# ethero_v4.net
KiCad netlist of a schematic drawn in EAGLE
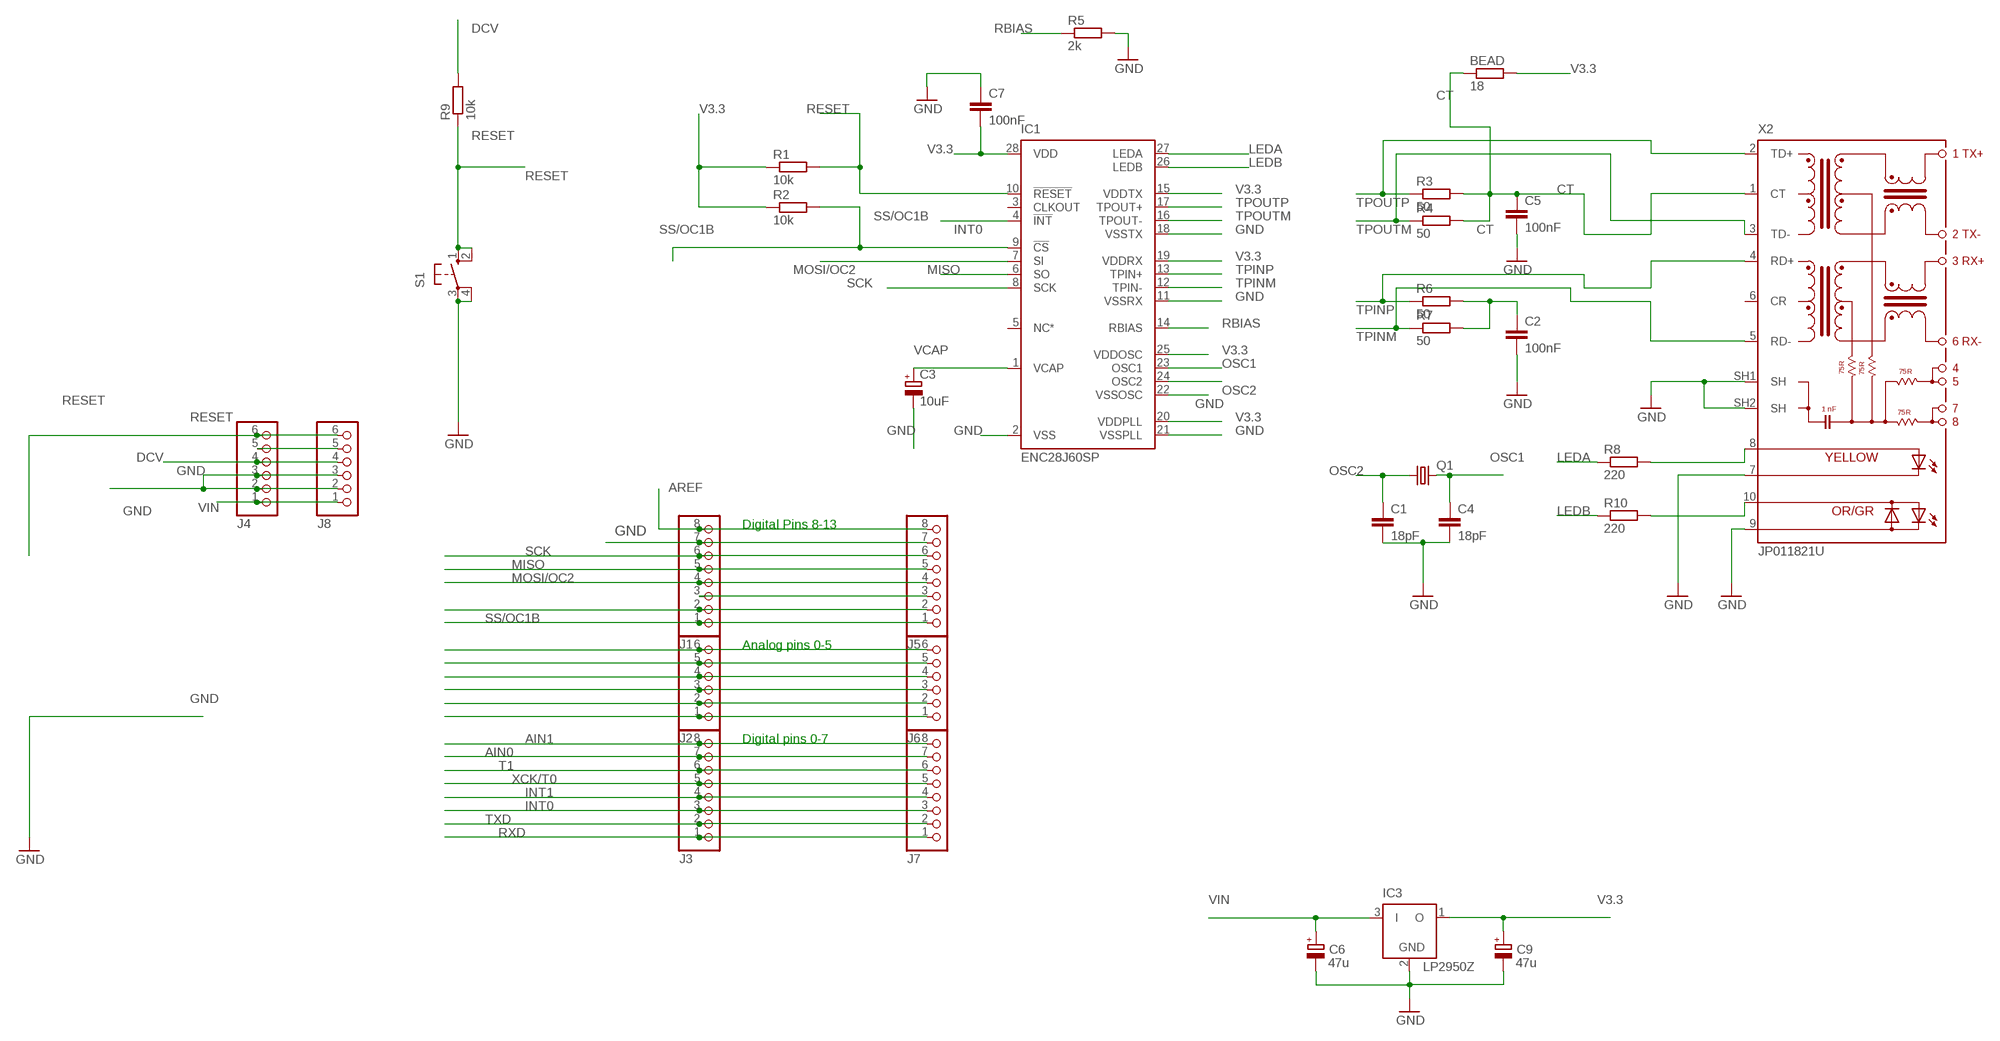
[diagram p0: schematic, sheet 1]

(export (version "E")
  (design (tool "Eeschema 10.0.6"))
  (components
    (comp (ref "BEAD")
      (value "18")
      (footprint "eagle-import:0204_7")
      (libsource (lib "eagle-import") (part "R-EU_0204/7"))
    )
    (comp (ref "C1")
      (value "18pF")
      (footprint "eagle-import:C025-025X050")
      (libsource (lib "eagle-import") (part "C-EU025-025X050"))
    )
    (comp (ref "C2")
      (value "100nF")
      (footprint "eagle-import:C025-025X050")
      (libsource (lib "eagle-import") (part "C-EU025-025X050"))
    )
    (comp (ref "C3")
      (value "10uF")
      (footprint "eagle-import:E5-5")
      (libsource (lib "eagle-import") (part "CPOL-EUE5-5"))
    )
    (comp (ref "C4")
      (value "18pF")
      (footprint "eagle-import:C025-025X050")
      (libsource (lib "eagle-import") (part "C-EU025-025X050"))
    )
    (comp (ref "C5")
      (value "100nF")
      (footprint "eagle-import:C025-025X050")
      (libsource (lib "eagle-import") (part "C-EU025-025X050"))
    )
    (comp (ref "C6")
      (value "47u")
      (footprint "eagle-import:E3,5-8")
      (libsource (lib "eagle-import") (part "CPOL-EUE3.5-8"))
    )
    (comp (ref "C7")
      (value "100nF")
      (footprint "eagle-import:C025-025X050")
      (libsource (lib "eagle-import") (part "C-EU025-025X050"))
    )
    (comp (ref "C9")
      (value "47u")
      (footprint "eagle-import:E3,5-8")
      (libsource (lib "eagle-import") (part "CPOL-EUE3.5-8"))
    )
    (comp (ref "IC1")
      (value "ENC28J60SP")
      (footprint "eagle-import:DIL28-3")
      (fields (field (name "MF") "MICROCHIP") (field (name "MPN") "ENC28J60/SP"))
      (libsource (lib "eagle-import") (part "ENC28J60SP"))
    )
    (comp (ref "IC3")
      (value "LP2950Z")
      (footprint "eagle-import:TO92")
      (libsource (lib "eagle-import") (part "LP2950Z"))
    )
    (comp (ref "J1")
      (value "PINHD-1X8")
      (footprint "eagle-import:1X08")
      (libsource (lib "eagle-import") (part "PINHD-1X8"))
    )
    (comp (ref "J2")
      (value "PINHD-1X6")
      (footprint "eagle-import:1X06")
      (libsource (lib "eagle-import") (part "PINHD-1X6"))
    )
    (comp (ref "J3")
      (value "PINHD-1X8")
      (footprint "eagle-import:1X08")
      (libsource (lib "eagle-import") (part "PINHD-1X8"))
    )
    (comp (ref "J4")
      (value "PINHD-1X6")
      (footprint "eagle-import:1X06")
      (libsource (lib "eagle-import") (part "PINHD-1X6"))
    )
    (comp (ref "J5")
      (value "PINHD-1X8")
      (footprint "eagle-import:1X08")
      (libsource (lib "eagle-import") (part "PINHD-1X8"))
    )
    (comp (ref "J6")
      (value "PINHD-1X6")
      (footprint "eagle-import:1X06")
      (libsource (lib "eagle-import") (part "PINHD-1X6"))
    )
    (comp (ref "J7")
      (value "PINHD-1X8")
      (footprint "eagle-import:1X08")
      (libsource (lib "eagle-import") (part "PINHD-1X8"))
    )
    (comp (ref "J8")
      (value "PINHD-1X6")
      (footprint "eagle-import:1X06")
      (libsource (lib "eagle-import") (part "PINHD-1X6"))
    )
    (comp (ref "Q1")
      (value "CRYSTALHC18U-V")
      (footprint "eagle-import:HC18U-V")
      (libsource (lib "eagle-import") (part "CRYSTALHC18U-V"))
    )
    (comp (ref "R1")
      (value "10k")
      (footprint "eagle-import:0204_7")
      (libsource (lib "eagle-import") (part "R-EU_0204/7"))
    )
    (comp (ref "R2")
      (value "10k")
      (footprint "eagle-import:0204_7")
      (libsource (lib "eagle-import") (part "R-EU_0204/7"))
    )
    (comp (ref "R3")
      (value "50")
      (footprint "eagle-import:0204_7")
      (libsource (lib "eagle-import") (part "R-EU_0204/7"))
    )
    (comp (ref "R4")
      (value "50")
      (footprint "eagle-import:0204_7")
      (libsource (lib "eagle-import") (part "R-EU_0204/7"))
    )
    (comp (ref "R5")
      (value "2k")
      (footprint "eagle-import:0204_7")
      (libsource (lib "eagle-import") (part "R-EU_0204/7"))
    )
    (comp (ref "R6")
      (value "50")
      (footprint "eagle-import:0204_7")
      (libsource (lib "eagle-import") (part "R-EU_0204/7"))
    )
    (comp (ref "R7")
      (value "50")
      (footprint "eagle-import:0204_7")
      (libsource (lib "eagle-import") (part "R-EU_0204/7"))
    )
    (comp (ref "R8")
      (value "220")
      (footprint "eagle-import:0204_7")
      (libsource (lib "eagle-import") (part "R-EU_0204/7"))
    )
    (comp (ref "R9")
      (value "10k")
      (footprint "eagle-import:0204_7")
      (libsource (lib "eagle-import") (part "R-EU_0204/7"))
    )
    (comp (ref "R10")
      (value "220")
      (footprint "eagle-import:0204_7")
      (libsource (lib "eagle-import") (part "R-EU_0204/7"))
    )
    (comp (ref "S1")
      (value "10-XX")
      (footprint "eagle-import:B3F-10XX")
      (fields (field (name "MPN") "B3F-1000"))
      (libsource (lib "eagle-import") (part "10-XX"))
    )
    (comp (ref "X2")
      (value "JP011821U")
      (footprint "eagle-import:JP")
      (libsource (lib "eagle-import") (part "JP011821U"))
    )
  )
  (nets
    (net (code "1") (name "/AIN0") (class "Default")
      (node (ref "J3") (pin "7") (pinfunction "7_7") (pintype "passive"))
      (node (ref "J7") (pin "7") (pinfunction "7_7") (pintype "passive"))
    )
    (net (code "2") (name "/AIN1") (class "Default")
      (node (ref "J3") (pin "8") (pinfunction "8_8") (pintype "passive"))
      (node (ref "J7") (pin "8") (pinfunction "8_8") (pintype "passive"))
    )
    (net (code "3") (name "/AREF") (class "Default")
      (node (ref "J1") (pin "8") (pinfunction "8_8") (pintype "passive"))
      (node (ref "J5") (pin "8") (pinfunction "8_8") (pintype "passive"))
    )
    (net (code "4") (name "/CT") (class "Default")
      (node (ref "BEAD") (pin "1") (pinfunction "1_1") (pintype "passive"))
      (node (ref "C5") (pin "1") (pinfunction "1_1") (pintype "passive"))
      (node (ref "R3") (pin "2") (pinfunction "2_2") (pintype "passive"))
      (node (ref "R4") (pin "2") (pinfunction "2_2") (pintype "passive"))
      (node (ref "X2") (pin "1") (pinfunction "CT_1") (pintype "input"))
    )
    (net (code "5") (name "/DCV") (class "Default")
      (node (ref "J4") (pin "4") (pinfunction "4_4") (pintype "passive"))
      (node (ref "J8") (pin "4") (pinfunction "4_4") (pintype "passive"))
      (node (ref "R9") (pin "2") (pinfunction "2_2") (pintype "passive"))
    )
    (net (code "6") (name "/INT0") (class "Default")
      (node (ref "IC1") (pin "4") (pinfunction "~{INT}_4") (pintype "output"))
      (node (ref "J3") (pin "3") (pinfunction "3_3") (pintype "passive"))
      (node (ref "J7") (pin "3") (pinfunction "3_3") (pintype "passive"))
    )
    (net (code "7") (name "/INT1") (class "Default")
      (node (ref "J3") (pin "4") (pinfunction "4_4") (pintype "passive"))
      (node (ref "J7") (pin "4") (pinfunction "4_4") (pintype "passive"))
    )
    (net (code "8") (name "/LEDA") (class "Default")
      (node (ref "IC1") (pin "27") (pinfunction "LEDA_27") (pintype "output"))
      (node (ref "R8") (pin "1") (pinfunction "1_1") (pintype "passive"))
    )
    (net (code "9") (name "/LEDB") (class "Default")
      (node (ref "IC1") (pin "26") (pinfunction "LEDB_26") (pintype "output"))
      (node (ref "R10") (pin "1") (pinfunction "1_1") (pintype "passive"))
    )
    (net (code "10") (name "/MISO") (class "Default")
      (node (ref "IC1") (pin "6") (pinfunction "SO_6") (pintype "output"))
      (node (ref "J1") (pin "5") (pinfunction "5_5") (pintype "passive"))
      (node (ref "J5") (pin "5") (pinfunction "5_5") (pintype "passive"))
    )
    (net (code "11") (name "/MOSI{slash}OC2") (class "Default")
      (node (ref "IC1") (pin "7") (pinfunction "SI_7") (pintype "input"))
      (node (ref "J1") (pin "4") (pinfunction "4_4") (pintype "passive"))
      (node (ref "J5") (pin "4") (pinfunction "4_4") (pintype "passive"))
    )
    (net (code "12") (name "/OSC1") (class "Default")
      (node (ref "C4") (pin "1") (pinfunction "1_1") (pintype "passive"))
      (node (ref "IC1") (pin "23") (pinfunction "OSC1_23") (pintype "input"))
      (node (ref "Q1") (pin "2") (pinfunction "2_2") (pintype "passive"))
    )
    (net (code "13") (name "/OSC2") (class "Default")
      (node (ref "C1") (pin "1") (pinfunction "1_1") (pintype "passive"))
      (node (ref "IC1") (pin "24") (pinfunction "OSC2_24") (pintype "output"))
      (node (ref "Q1") (pin "1") (pinfunction "1_1") (pintype "passive"))
    )
    (net (code "14") (name "/RBIAS") (class "Default")
      (node (ref "IC1") (pin "14") (pinfunction "RBIAS_14") (pintype "input"))
      (node (ref "R5") (pin "1") (pinfunction "1_1") (pintype "passive"))
    )
    (net (code "15") (name "/RESET") (class "Default")
      (node (ref "IC1") (pin "10") (pinfunction "~{RESET}_10") (pintype "input"))
      (node (ref "J4") (pin "6") (pinfunction "6_6") (pintype "passive"))
      (node (ref "J8") (pin "6") (pinfunction "6_6") (pintype "passive"))
      (node (ref "R1") (pin "2") (pinfunction "2_2") (pintype "passive"))
      (node (ref "R9") (pin "1") (pinfunction "1_1") (pintype "passive"))
      (node (ref "S1") (pin "1") (pinfunction "S_1") (pintype "passive"))
      (node (ref "S1") (pin "2") (pinfunction "S1_2") (pintype "passive"))
    )
    (net (code "16") (name "/RXD") (class "Default")
      (node (ref "J3") (pin "1") (pinfunction "1_1") (pintype "passive"))
      (node (ref "J7") (pin "1") (pinfunction "1_1") (pintype "passive"))
    )
    (net (code "17") (name "/SCK") (class "Default")
      (node (ref "IC1") (pin "8") (pinfunction "SCK_8") (pintype "input"))
      (node (ref "J1") (pin "6") (pinfunction "6_6") (pintype "passive"))
      (node (ref "J5") (pin "6") (pinfunction "6_6") (pintype "passive"))
    )
    (net (code "18") (name "/SS{slash}OC1B") (class "Default")
      (node (ref "IC1") (pin "9") (pinfunction "~{CS}_9") (pintype "input"))
      (node (ref "J1") (pin "1") (pinfunction "1_1") (pintype "passive"))
      (node (ref "J5") (pin "1") (pinfunction "1_1") (pintype "passive"))
      (node (ref "R2") (pin "2") (pinfunction "2_2") (pintype "passive"))
    )
    (net (code "19") (name "/T1") (class "Default")
      (node (ref "J3") (pin "6") (pinfunction "6_6") (pintype "passive"))
      (node (ref "J7") (pin "6") (pinfunction "6_6") (pintype "passive"))
    )
    (net (code "20") (name "/TPINM") (class "Default")
      (node (ref "IC1") (pin "12") (pinfunction "TPIN-_12") (pintype "input"))
      (node (ref "R7") (pin "1") (pinfunction "1_1") (pintype "passive"))
      (node (ref "X2") (pin "5") (pinfunction "RD-_5") (pintype "input"))
    )
    (net (code "21") (name "/TPINP") (class "Default")
      (node (ref "IC1") (pin "13") (pinfunction "TPIN+_13") (pintype "input"))
      (node (ref "R6") (pin "1") (pinfunction "1_1") (pintype "passive"))
      (node (ref "X2") (pin "4") (pinfunction "RD+_4") (pintype "input"))
    )
    (net (code "22") (name "/TPOUTM") (class "Default")
      (node (ref "IC1") (pin "16") (pinfunction "TPOUT-_16") (pintype "output"))
      (node (ref "R4") (pin "1") (pinfunction "1_1") (pintype "passive"))
      (node (ref "X2") (pin "3") (pinfunction "TD-_3") (pintype "input"))
    )
    (net (code "23") (name "/TPOUTP") (class "Default")
      (node (ref "IC1") (pin "17") (pinfunction "TPOUT+_17") (pintype "output"))
      (node (ref "R3") (pin "1") (pinfunction "1_1") (pintype "passive"))
      (node (ref "X2") (pin "2") (pinfunction "TD+_2") (pintype "input"))
    )
    (net (code "24") (name "/TXD") (class "Default")
      (node (ref "J3") (pin "2") (pinfunction "2_2") (pintype "passive"))
      (node (ref "J7") (pin "2") (pinfunction "2_2") (pintype "passive"))
    )
    (net (code "25") (name "/V3.3") (class "Default")
      (node (ref "BEAD") (pin "2") (pinfunction "2_2") (pintype "passive"))
      (node (ref "C7") (pin "2") (pinfunction "2_2") (pintype "passive"))
      (node (ref "C9") (pin "+") (pinfunction "+_+") (pintype "passive"))
      (node (ref "IC1") (pin "15") (pinfunction "VDDTX_15") (pintype "input"))
      (node (ref "IC1") (pin "19") (pinfunction "VDDRX_19") (pintype "input"))
      (node (ref "IC1") (pin "20") (pinfunction "VDDPLL_20") (pintype "input"))
      (node (ref "IC1") (pin "25") (pinfunction "VDDOSC_25") (pintype "input"))
      (node (ref "IC1") (pin "28") (pinfunction "VDD_28") (pintype "input"))
      (node (ref "IC3") (pin "1") (pinfunction "O_1") (pintype "input"))
      (node (ref "R1") (pin "1") (pinfunction "1_1") (pintype "passive"))
      (node (ref "R2") (pin "1") (pinfunction "1_1") (pintype "passive"))
    )
    (net (code "26") (name "/VCAP") (class "Default")
      (node (ref "C3") (pin "+") (pinfunction "+_+") (pintype "passive"))
      (node (ref "IC1") (pin "1") (pinfunction "VCAP_1") (pintype "input"))
    )
    (net (code "27") (name "/VIN") (class "Default")
      (node (ref "C6") (pin "+") (pinfunction "+_+") (pintype "passive"))
      (node (ref "IC3") (pin "3") (pinfunction "I_3") (pintype "input"))
      (node (ref "J4") (pin "1") (pinfunction "1_1") (pintype "passive"))
      (node (ref "J8") (pin "1") (pinfunction "1_1") (pintype "passive"))
    )
    (net (code "28") (name "/XCK{slash}T0") (class "Default")
      (node (ref "J3") (pin "5") (pinfunction "5_5") (pintype "passive"))
      (node (ref "J7") (pin "5") (pinfunction "5_5") (pintype "passive"))
    )
    (net (code "29") (name "GND") (class "Default")
      (node (ref "C1") (pin "2") (pinfunction "2_2") (pintype "passive"))
      (node (ref "C2") (pin "2") (pinfunction "2_2") (pintype "passive"))
      (node (ref "C3") (pin "-") (pinfunction "-_-") (pintype "passive"))
      (node (ref "C4") (pin "2") (pinfunction "2_2") (pintype "passive"))
      (node (ref "C5") (pin "2") (pinfunction "2_2") (pintype "passive"))
      (node (ref "C6") (pin "-") (pinfunction "-_-") (pintype "passive"))
      (node (ref "C7") (pin "1") (pinfunction "1_1") (pintype "passive"))
      (node (ref "C9") (pin "-") (pinfunction "-_-") (pintype "passive"))
      (node (ref "IC1") (pin "11") (pinfunction "VSSRX_11") (pintype "input"))
      (node (ref "IC1") (pin "18") (pinfunction "VSSTX_18") (pintype "input"))
      (node (ref "IC1") (pin "2") (pinfunction "VSS_2") (pintype "input"))
      (node (ref "IC1") (pin "21") (pinfunction "VSSPLL_21") (pintype "input"))
      (node (ref "IC1") (pin "22") (pinfunction "VSSOSC_22") (pintype "input"))
      (node (ref "IC3") (pin "2") (pinfunction "GND_2") (pintype "power_in"))
      (node (ref "J1") (pin "7") (pinfunction "7_7") (pintype "passive"))
      (node (ref "J4") (pin "2") (pinfunction "2_2") (pintype "passive"))
      (node (ref "J4") (pin "3") (pinfunction "3_3") (pintype "passive"))
      (node (ref "J5") (pin "7") (pinfunction "7_7") (pintype "passive"))
      (node (ref "J8") (pin "2") (pinfunction "2_2") (pintype "passive"))
      (node (ref "J8") (pin "3") (pinfunction "3_3") (pintype "passive"))
      (node (ref "R5") (pin "2") (pinfunction "2_2") (pintype "passive"))
      (node (ref "S1") (pin "3") (pinfunction "P_3") (pintype "passive"))
      (node (ref "S1") (pin "4") (pinfunction "P1_4") (pintype "passive"))
      (node (ref "X2") (pin "7") (pinfunction "C-Y_7") (pintype "input"))
      (node (ref "X2") (pin "9") (pinfunction "A-O_C-G_9") (pintype "input"))
      (node (ref "X2") (pin "SH1") (pinfunction "SH_SH1") (pintype "input"))
      (node (ref "X2") (pin "SH2") (pinfunction "SH_SH2") (pintype "input"))
    )
    (net (code "30") (name "Net-(C2-Pad1)") (class "Default")
      (node (ref "C2") (pin "1") (pinfunction "1_1") (pintype "passive"))
      (node (ref "R6") (pin "2") (pinfunction "2_2") (pintype "passive"))
      (node (ref "R7") (pin "2") (pinfunction "2_2") (pintype "passive"))
    )
    (net (code "31") (name "Net-(J1-Pad2)") (class "Default")
      (node (ref "J1") (pin "2") (pinfunction "2_2") (pintype "passive"))
      (node (ref "J5") (pin "2") (pinfunction "2_2") (pintype "passive"))
    )
    (net (code "32") (name "Net-(J1-Pad3)") (class "Default")
      (node (ref "J1") (pin "3") (pinfunction "3_3") (pintype "passive"))
      (node (ref "J5") (pin "3") (pinfunction "3_3") (pintype "passive"))
    )
    (net (code "33") (name "Net-(J2-Pad1)") (class "Default")
      (node (ref "J2") (pin "1") (pinfunction "1_1") (pintype "passive"))
      (node (ref "J6") (pin "1") (pinfunction "1_1") (pintype "passive"))
    )
    (net (code "34") (name "Net-(J2-Pad2)") (class "Default")
      (node (ref "J2") (pin "2") (pinfunction "2_2") (pintype "passive"))
      (node (ref "J6") (pin "2") (pinfunction "2_2") (pintype "passive"))
    )
    (net (code "35") (name "Net-(J2-Pad3)") (class "Default")
      (node (ref "J2") (pin "3") (pinfunction "3_3") (pintype "passive"))
      (node (ref "J6") (pin "3") (pinfunction "3_3") (pintype "passive"))
    )
    (net (code "36") (name "Net-(J2-Pad4)") (class "Default")
      (node (ref "J2") (pin "4") (pinfunction "4_4") (pintype "passive"))
      (node (ref "J6") (pin "4") (pinfunction "4_4") (pintype "passive"))
    )
    (net (code "37") (name "Net-(J2-Pad5)") (class "Default")
      (node (ref "J2") (pin "5") (pinfunction "5_5") (pintype "passive"))
      (node (ref "J6") (pin "5") (pinfunction "5_5") (pintype "passive"))
    )
    (net (code "38") (name "Net-(J2-Pad6)") (class "Default")
      (node (ref "J2") (pin "6") (pinfunction "6_6") (pintype "passive"))
      (node (ref "J6") (pin "6") (pinfunction "6_6") (pintype "passive"))
    )
    (net (code "39") (name "Net-(J4-Pad5)") (class "Default")
      (node (ref "J4") (pin "5") (pinfunction "5_5") (pintype "passive"))
      (node (ref "J8") (pin "5") (pinfunction "5_5") (pintype "passive"))
    )
    (net (code "40") (name "Net-(X2-A-Y)") (class "Default")
      (node (ref "R8") (pin "2") (pinfunction "2_2") (pintype "passive"))
      (node (ref "X2") (pin "8") (pinfunction "A-Y_8") (pintype "input"))
    )
    (net (code "41") (name "Net-(X2-C-O_A-G)") (class "Default")
      (node (ref "R10") (pin "2") (pinfunction "2_2") (pintype "passive"))
      (node (ref "X2") (pin "10") (pinfunction "C-O_A-G_10") (pintype "input"))
    )
    (net (code "42") (name "unconnected-(IC1-CLKOUT-Pad3)") (class "Default")
      (node (ref "IC1") (pin "3") (pinfunction "CLKOUT_3") (pintype "output"))
    )
    (net (code "43") (name "unconnected-(IC1-NC*-Pad5)") (class "Default")
      (node (ref "IC1") (pin "5") (pinfunction "NC*_5") (pintype "output"))
    )
    (net (code "44") (name "unconnected-(X2-CR-Pad6)") (class "Default")
      (node (ref "X2") (pin "6") (pinfunction "CR_6") (pintype "input"))
    )
  )
)
